# 28_Pins.net
KiCad netlist of a schematic drawn in Altium Designer
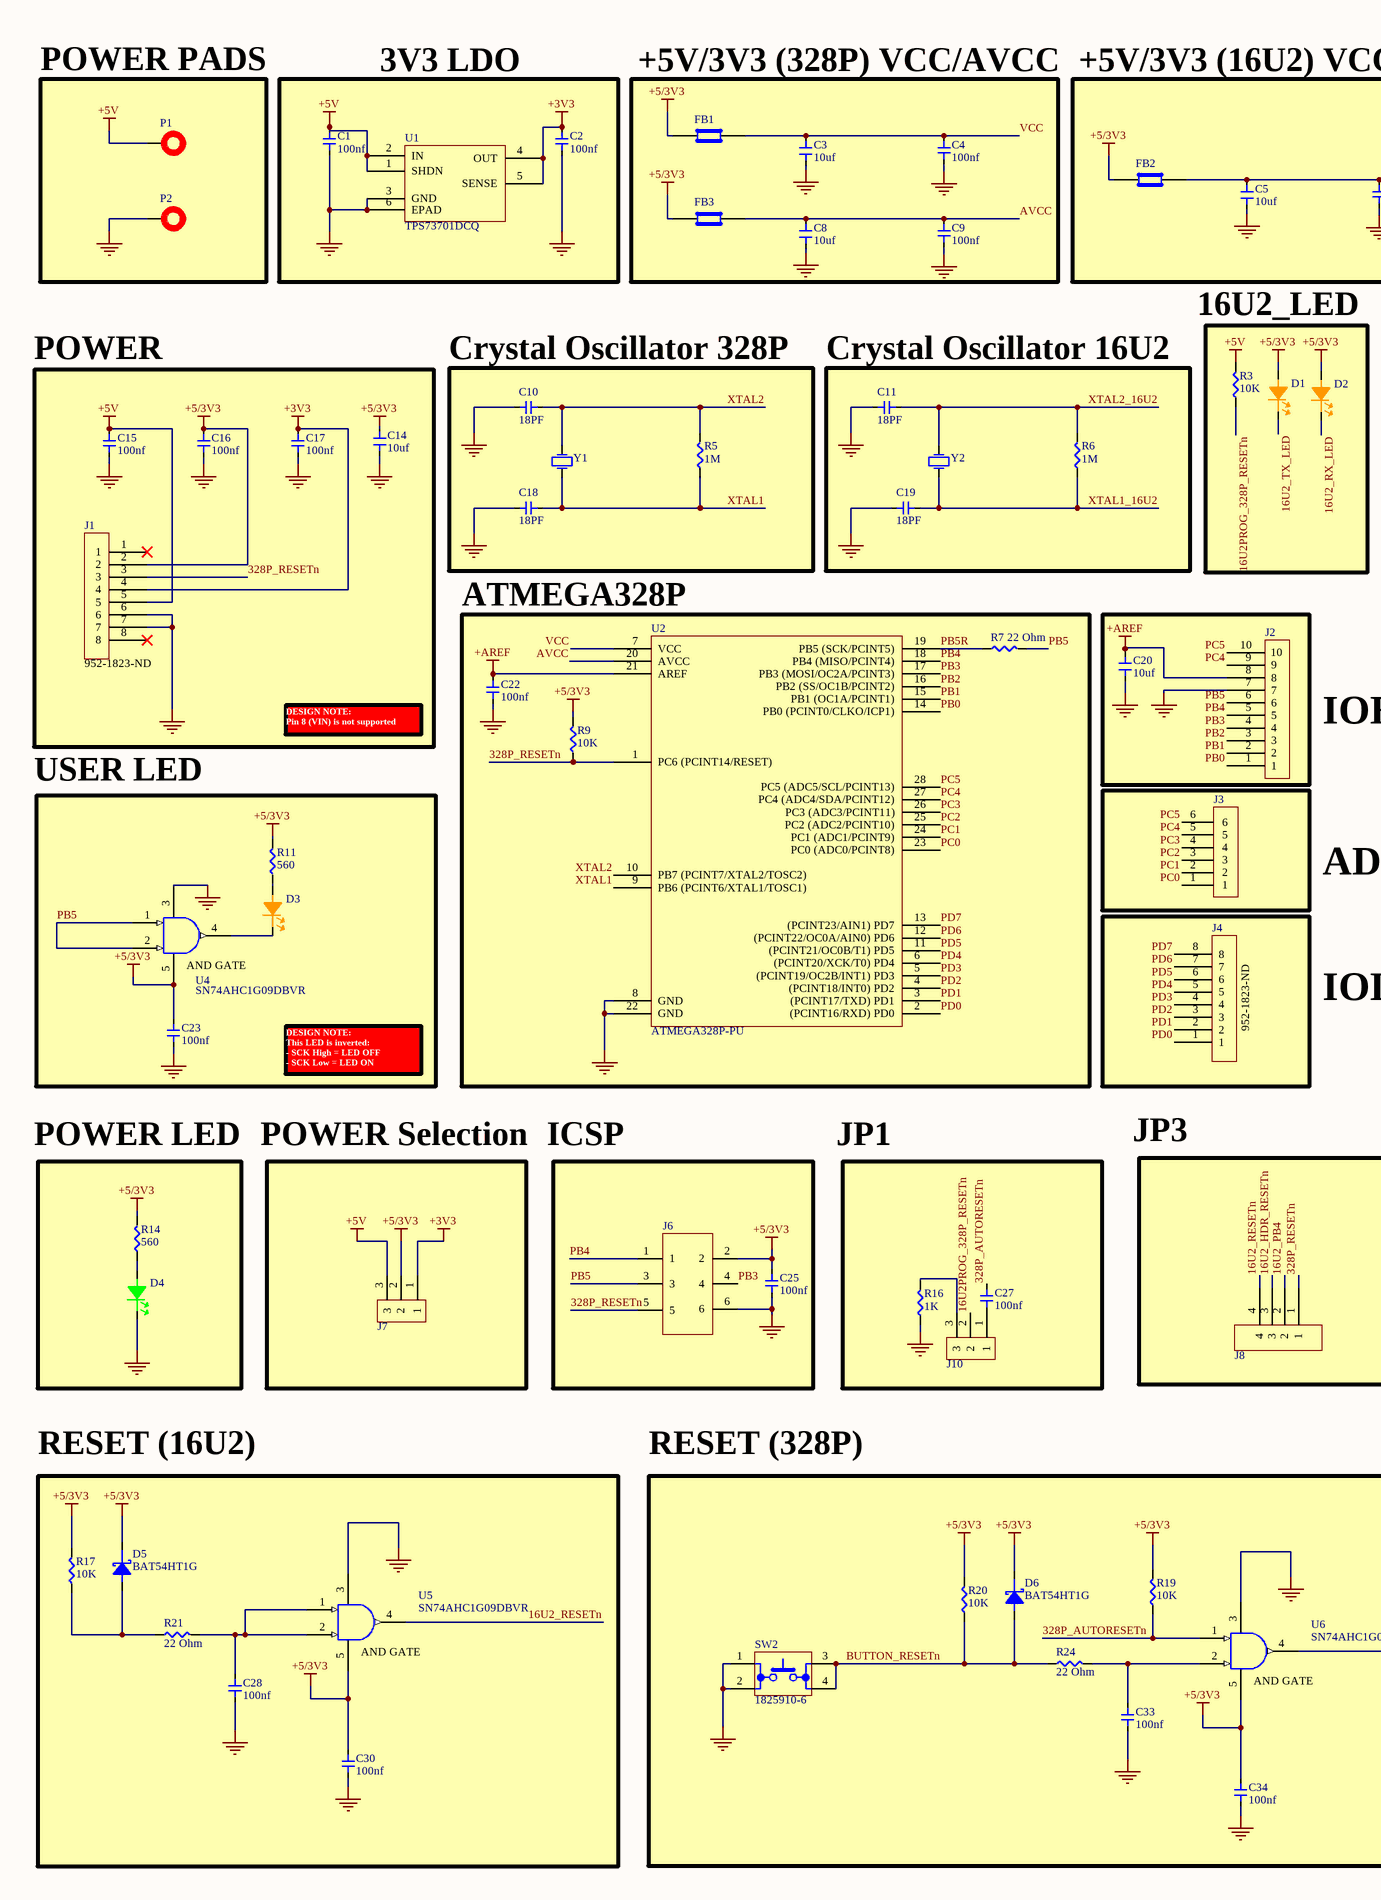
[diagram p0: 28_Pins.SchDoc, left]
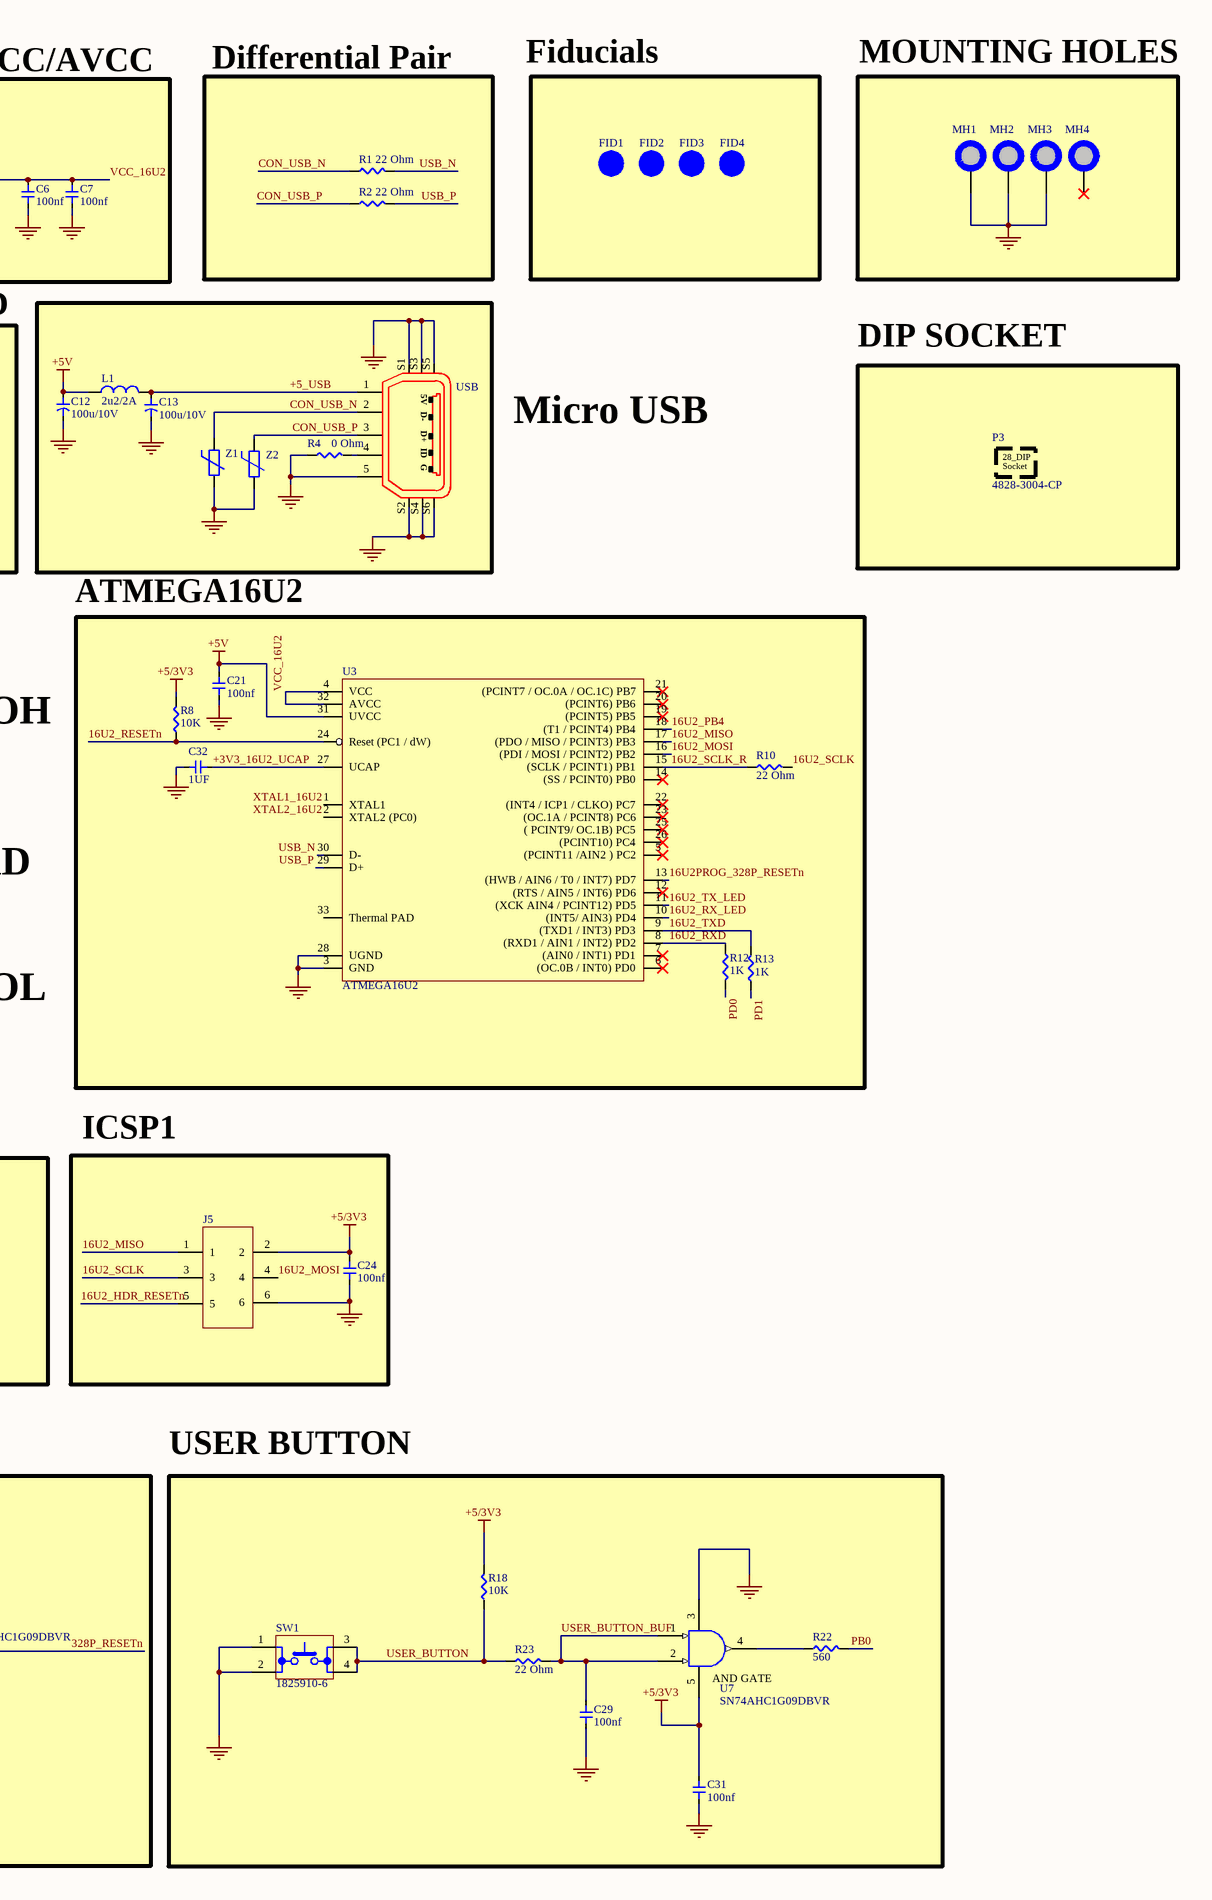
[diagram p1: 28_Pins.SchDoc, right]

(export (version "E")
  (design (tool "Eeschema 10.0.6"))
  (components
    (comp (ref "C1")
      (value "100nf")
      (footprint "Cap_100nf")
      (description "C Series 0805 0.1 uF 50 V ±10 % Tolerance X7R SMT Multilayer Ceramic Capacitor")
      (fields
        (field (name "MANUFACTURER") "TDK")
        (field (name "MANUFACTURER PART NUMBER") "C2012X7R1H104K085AA")
      )
      (libsource (lib "Schlib") (part "C2012X7R1H104K085AA"))
    )
    (comp (ref "C2")
      (value "100nf")
      (footprint "Cap_100nf")
      (description "C Series 0805 0.1 uF 50 V ±10 % Tolerance X7R SMT Multilayer Ceramic Capacitor")
      (fields
        (field (name "MANUFACTURER") "TDK")
        (field (name "MANUFACTURER PART NUMBER") "C2012X7R1H104K085AA")
      )
      (libsource (lib "Schlib") (part "C2012X7R1H104K085AA"))
    )
    (comp (ref "C3")
      (value "10uf")
      (footprint "Cap_10uf")
      (fields
        (field (name "MANUFACTURER") "TDK")
        (field (name "MANUFACTURER PART NUMBER") "C2012X5R1C106M125AC")
        (field (name "TOLERANCE") "20%")
      )
      (libsource (lib "Schlib") (part "C2012X5R1C106M125AC"))
    )
    (comp (ref "C4")
      (value "100nf")
      (footprint "Cap_100nf")
      (description "C Series 0805 0.1 uF 50 V ±10 % Tolerance X7R SMT Multilayer Ceramic Capacitor")
      (fields
        (field (name "MANUFACTURER") "TDK")
        (field (name "MANUFACTURER PART NUMBER") "C2012X7R1H104K085AA")
      )
      (libsource (lib "Schlib") (part "C2012X7R1H104K085AA"))
    )
    (comp (ref "C5")
      (value "10uf")
      (footprint "Cap_10uf")
      (fields
        (field (name "MANUFACTURER") "TDK")
        (field (name "MANUFACTURER PART NUMBER") "C2012X5R1C106M125AC")
        (field (name "TOLERANCE") "20%")
      )
      (libsource (lib "Schlib") (part "C2012X5R1C106M125AC"))
    )
    (comp (ref "C6")
      (value "100nf")
      (footprint "Cap_100nf")
      (description "C Series 0805 0.1 uF 50 V ±10 % Tolerance X7R SMT Multilayer Ceramic Capacitor")
      (fields
        (field (name "MANUFACTURER") "TDK")
        (field (name "MANUFACTURER PART NUMBER") "C2012X7R1H104K085AA")
      )
      (libsource (lib "Schlib") (part "C2012X7R1H104K085AA"))
    )
    (comp (ref "C7")
      (value "100nf")
      (footprint "Cap_100nf")
      (description "C Series 0805 0.1 uF 50 V ±10 % Tolerance X7R SMT Multilayer Ceramic Capacitor")
      (fields
        (field (name "MANUFACTURER") "TDK")
        (field (name "MANUFACTURER PART NUMBER") "C2012X7R1H104K085AA")
      )
      (libsource (lib "Schlib") (part "C2012X7R1H104K085AA"))
    )
    (comp (ref "C8")
      (value "10uf")
      (footprint "Cap_10uf")
      (fields
        (field (name "MANUFACTURER") "TDK")
        (field (name "MANUFACTURER PART NUMBER") "C2012X5R1C106M125AC")
        (field (name "TOLERANCE") "20%")
      )
      (libsource (lib "Schlib") (part "C2012X5R1C106M125AC"))
    )
    (comp (ref "C9")
      (value "100nf")
      (footprint "Cap_100nf")
      (description "C Series 0805 0.1 uF 50 V ±10 % Tolerance X7R SMT Multilayer Ceramic Capacitor")
      (fields
        (field (name "MANUFACTURER") "TDK")
        (field (name "MANUFACTURER PART NUMBER") "C2012X7R1H104K085AA")
      )
      (libsource (lib "Schlib") (part "C2012X7R1H104K085AA"))
    )
    (comp (ref "C10")
      (value "18PF")
      (footprint "Cap_100nf")
      (description "Ceramic Capacitor 0.079Lx0.049W 2.00mmx1.25mm C0G NP0 ±5% 18pF")
      (fields
        (field (name "MANUFACTURER") "KEMET")
        (field (name "MANUFACTURER PART NUMBER") "C0805C180J5GACTU")
      )
      (libsource (lib "Schlib") (part "C0805C180J5GACTU"))
    )
    (comp (ref "C11")
      (value "18PF")
      (footprint "Cap_100nf")
      (description "Ceramic Capacitor 0.079Lx0.049W 2.00mmx1.25mm C0G NP0 ±5% 18pF")
      (fields
        (field (name "MANUFACTURER") "KEMET")
        (field (name "MANUFACTURER PART NUMBER") "C0805C180J5GACTU")
      )
      (libsource (lib "Schlib") (part "C0805C180J5GACTU"))
    )
    (comp (ref "C12")
      (value "100u/10V")
      (footprint "Capacitor100uf")
      (description "Radial Can - SMD ALUMINUM ELECTROLYTIC CAPACITOR S 10V 100muF ±20% 0.197Dia 5.00mm")
      (fields
        (field (name "MANUFACTURER") "Panasonic")
        (field (name "MANUFACTURER PART NUMBER") "EEE-1AA101WR")
      )
      (libsource (lib "Schlib") (part "EEE-1AA101WR"))
    )
    (comp (ref "C13")
      (value "100u/10V")
      (footprint "Capacitor100uf")
      (description "Radial Can - SMD ALUMINUM ELECTROLYTIC CAPACITOR S 10V 100muF ±20% 0.197Dia 5.00mm")
      (fields
        (field (name "MANUFACTURER") "Panasonic")
        (field (name "MANUFACTURER PART NUMBER") "EEE-1AA101WR")
      )
      (libsource (lib "Schlib") (part "EEE-1AA101WR"))
    )
    (comp (ref "C14")
      (value "10uf")
      (footprint "Cap_10uf")
      (fields
        (field (name "MANUFACTURER") "TDK")
        (field (name "MANUFACTURER PART NUMBER") "C2012X5R1C106M125AC")
        (field (name "TOLERANCE") "20%")
      )
      (libsource (lib "Schlib") (part "C2012X5R1C106M125AC"))
    )
    (comp (ref "C15")
      (value "100nf")
      (footprint "Cap_100nf")
      (description "C Series 0805 0.1 uF 50 V ±10 % Tolerance X7R SMT Multilayer Ceramic Capacitor")
      (fields
        (field (name "MANUFACTURER") "TDK")
        (field (name "MANUFACTURER PART NUMBER") "C2012X7R1H104K085AA")
      )
      (libsource (lib "Schlib") (part "C2012X7R1H104K085AA"))
    )
    (comp (ref "C16")
      (value "100nf")
      (footprint "Cap_100nf")
      (description "C Series 0805 0.1 uF 50 V ±10 % Tolerance X7R SMT Multilayer Ceramic Capacitor")
      (fields
        (field (name "MANUFACTURER") "TDK")
        (field (name "MANUFACTURER PART NUMBER") "C2012X7R1H104K085AA")
      )
      (libsource (lib "Schlib") (part "C2012X7R1H104K085AA"))
    )
    (comp (ref "C17")
      (value "100nf")
      (footprint "Cap_100nf")
      (description "C Series 0805 0.1 uF 50 V ±10 % Tolerance X7R SMT Multilayer Ceramic Capacitor")
      (fields
        (field (name "MANUFACTURER") "TDK")
        (field (name "MANUFACTURER PART NUMBER") "C2012X7R1H104K085AA")
      )
      (libsource (lib "Schlib") (part "C2012X7R1H104K085AA"))
    )
    (comp (ref "C18")
      (value "18PF")
      (footprint "Cap_100nf")
      (description "Ceramic Capacitor 0.079Lx0.049W 2.00mmx1.25mm C0G NP0 ±5% 18pF")
      (fields
        (field (name "MANUFACTURER") "KEMET")
        (field (name "MANUFACTURER PART NUMBER") "C0805C180J5GACTU")
      )
      (libsource (lib "Schlib") (part "C0805C180J5GACTU"))
    )
    (comp (ref "C19")
      (value "18PF")
      (footprint "Cap_100nf")
      (description "Ceramic Capacitor 0.079Lx0.049W 2.00mmx1.25mm C0G NP0 ±5% 18pF")
      (fields
        (field (name "MANUFACTURER") "KEMET")
        (field (name "MANUFACTURER PART NUMBER") "C0805C180J5GACTU")
      )
      (libsource (lib "Schlib") (part "C0805C180J5GACTU"))
    )
    (comp (ref "C20")
      (value "10uf")
      (footprint "Cap_10uf")
      (fields
        (field (name "MANUFACTURER") "TDK")
        (field (name "MANUFACTURER PART NUMBER") "C2012X5R1C106M125AC")
        (field (name "TOLERANCE") "20%")
      )
      (libsource (lib "Schlib") (part "C2012X5R1C106M125AC"))
    )
    (comp (ref "C21")
      (value "100nf")
      (footprint "Cap_100nf")
      (description "C Series 0805 0.1 uF 50 V ±10 % Tolerance X7R SMT Multilayer Ceramic Capacitor")
      (fields
        (field (name "MANUFACTURER") "TDK")
        (field (name "MANUFACTURER PART NUMBER") "C2012X7R1H104K085AA")
      )
      (libsource (lib "Schlib") (part "C2012X7R1H104K085AA"))
    )
    (comp (ref "C22")
      (value "100nf")
      (footprint "Cap_100nf")
      (description "C Series 0805 0.1 uF 50 V ±10 % Tolerance X7R SMT Multilayer Ceramic Capacitor")
      (fields
        (field (name "MANUFACTURER") "TDK")
        (field (name "MANUFACTURER PART NUMBER") "C2012X7R1H104K085AA")
      )
      (libsource (lib "Schlib") (part "C2012X7R1H104K085AA"))
    )
    (comp (ref "C23")
      (value "100nf")
      (footprint "Cap_100nf")
      (description "C Series 0805 0.1 uF 50 V ±10 % Tolerance X7R SMT Multilayer Ceramic Capacitor")
      (fields
        (field (name "MANUFACTURER") "TDK")
        (field (name "MANUFACTURER PART NUMBER") "C2012X7R1H104K085AA")
      )
      (libsource (lib "Schlib") (part "C2012X7R1H104K085AA"))
    )
    (comp (ref "C24")
      (value "100nf")
      (footprint "Cap_100nf")
      (description "C Series 0805 0.1 uF 50 V ±10 % Tolerance X7R SMT Multilayer Ceramic Capacitor")
      (fields
        (field (name "MANUFACTURER") "TDK")
        (field (name "MANUFACTURER PART NUMBER") "C2012X7R1H104K085AA")
      )
      (libsource (lib "Schlib") (part "C2012X7R1H104K085AA"))
    )
    (comp (ref "C25")
      (value "100nf")
      (footprint "Cap_100nf")
      (description "C Series 0805 0.1 uF 50 V ±10 % Tolerance X7R SMT Multilayer Ceramic Capacitor")
      (fields
        (field (name "MANUFACTURER") "TDK")
        (field (name "MANUFACTURER PART NUMBER") "C2012X7R1H104K085AA")
      )
      (libsource (lib "Schlib") (part "C2012X7R1H104K085AA"))
    )
    (comp (ref "C27")
      (value "100nf")
      (footprint "Cap_100nf")
      (description "C Series 0805 0.1 uF 50 V ±10 % Tolerance X7R SMT Multilayer Ceramic Capacitor")
      (fields
        (field (name "MANUFACTURER") "TDK")
        (field (name "MANUFACTURER PART NUMBER") "C2012X7R1H104K085AA")
      )
      (libsource (lib "Schlib") (part "C2012X7R1H104K085AA"))
    )
    (comp (ref "C28")
      (value "100nf")
      (footprint "Cap_100nf")
      (description "C Series 0805 0.1 uF 50 V ±10 % Tolerance X7R SMT Multilayer Ceramic Capacitor")
      (fields
        (field (name "MANUFACTURER") "TDK")
        (field (name "MANUFACTURER PART NUMBER") "C2012X7R1H104K085AA")
      )
      (libsource (lib "Schlib") (part "C2012X7R1H104K085AA"))
    )
    (comp (ref "C29")
      (value "100nf")
      (footprint "Cap_100nf")
      (description "C Series 0805 0.1 uF 50 V ±10 % Tolerance X7R SMT Multilayer Ceramic Capacitor")
      (fields
        (field (name "MANUFACTURER") "TDK")
        (field (name "MANUFACTURER PART NUMBER") "C2012X7R1H104K085AA")
      )
      (libsource (lib "Schlib") (part "C2012X7R1H104K085AA"))
    )
    (comp (ref "C30")
      (value "100nf")
      (footprint "Cap_100nf")
      (description "C Series 0805 0.1 uF 50 V ±10 % Tolerance X7R SMT Multilayer Ceramic Capacitor")
      (fields
        (field (name "MANUFACTURER") "TDK")
        (field (name "MANUFACTURER PART NUMBER") "C2012X7R1H104K085AA")
      )
      (libsource (lib "Schlib") (part "C2012X7R1H104K085AA"))
    )
    (comp (ref "C31")
      (value "100nf")
      (footprint "Cap_100nf")
      (description "C Series 0805 0.1 uF 50 V ±10 % Tolerance X7R SMT Multilayer Ceramic Capacitor")
      (fields
        (field (name "MANUFACTURER") "TDK")
        (field (name "MANUFACTURER PART NUMBER") "C2012X7R1H104K085AA")
      )
      (libsource (lib "Schlib") (part "C2012X7R1H104K085AA"))
    )
    (comp (ref "C32")
      (value "1UF")
      (footprint "Cap_10uf")
      (description "C Series 0805 1 uF 25 V ±10% Tolerance X5R SMT Multilayer Ceramic Capacitor")
      (fields
        (field (name "MANUFACTURER") "TDK")
        (field (name "MANUFACTURER PART NUMBER") "C2012X5R1E105K125AA")
      )
      (libsource (lib "Schlib") (part "C2012X5R1E105K125AA"))
    )
    (comp (ref "C33")
      (value "100nf")
      (footprint "Cap_100nf")
      (description "C Series 0805 0.1 uF 50 V ±10 % Tolerance X7R SMT Multilayer Ceramic Capacitor")
      (fields
        (field (name "MANUFACTURER") "TDK")
        (field (name "MANUFACTURER PART NUMBER") "C2012X7R1H104K085AA")
      )
      (libsource (lib "Schlib") (part "C2012X7R1H104K085AA"))
    )
    (comp (ref "C34")
      (value "100nf")
      (footprint "Cap_100nf")
      (description "C Series 0805 0.1 uF 50 V ±10 % Tolerance X7R SMT Multilayer Ceramic Capacitor")
      (fields
        (field (name "MANUFACTURER") "TDK")
        (field (name "MANUFACTURER PART NUMBER") "C2012X7R1H104K085AA")
      )
      (libsource (lib "Schlib") (part "C2012X7R1H104K085AA"))
    )
    (comp (ref "D1")
      (value "LO L29K-H2K1-24-0-2-R18-Z")
      (footprint "LED Indication")
      (description "LED Uni-Color Orange 610nm Automotive 2-Pin Chip 0603(1608Metric) T/R")
      (fields (field (name "MANUFACTURER") "Osram"))
      (libsource (lib "Schlib") (part "LO L29K-H2K1-24-0-2-R18-Z"))
    )
    (comp (ref "D2")
      (value "LO L29K-H2K1-24-0-2-R18-Z")
      (footprint "LED Indication")
      (description "LED Uni-Color Orange 610nm Automotive 2-Pin Chip 0603(1608Metric) T/R")
      (fields (field (name "MANUFACTURER") "Osram"))
      (libsource (lib "Schlib") (part "LO L29K-H2K1-24-0-2-R18-Z"))
    )
    (comp (ref "D3")
      (value "LO L29K-H2K1-24-0-2-R18-Z")
      (footprint "LED Indication")
      (description "LED Uni-Color Orange 610nm Automotive 2-Pin Chip 0603(1608Metric) T/R")
      (fields (field (name "MANUFACTURER") "Osram"))
      (libsource (lib "Schlib") (part "LO L29K-H2K1-24-0-2-R18-Z"))
    )
    (comp (ref "D4")
      (value "LG L29K-G2J1-24-0-2-R18-Z")
      (footprint "LED Indication")
      (description "LED Uni-Color Green 572nm 2-Pin Chip 0603(1608Metric) T/R")
      (fields (field (name "MANUFACTURER") "Osram"))
      (libsource (lib "Schlib") (part "LG L29K-G2J1-24-0-2-R18-Z"))
    )
    (comp (ref "D5")
      (value "BAT54HT1G")
      (footprint "diode")
      (description "Small Signal Schottky Diode, Single, 30 V, 200 Ma, 800 Mv, 600 Ma, 150 C")
      (fields (field (name "MANUFACTURER") "onsemi"))
      (libsource (lib "Schlib") (part "BAT54HT1G"))
    )
    (comp (ref "D6")
      (value "BAT54HT1G")
      (footprint "diode")
      (description "Small Signal Schottky Diode, Single, 30 V, 200 Ma, 800 Mv, 600 Ma, 150 C")
      (fields (field (name "MANUFACTURER") "onsemi"))
      (libsource (lib "Schlib") (part "BAT54HT1G"))
    )
    (comp (ref "FB1")
      (value "MPZ2012S601AT000")
      (footprint "Cap_10uf")
      (description "Ferrite Beads Multi-Layer Power 600Ohm 25% 100MHz 2A 100mOhm DCR 0805 T/R")
      (fields (field (name "MANUFACTURER") "TDK") (field (name "TOLERANCE") "25%"))
      (libsource (lib "Schlib") (part "MPZ2012S601AT000"))
    )
    (comp (ref "FB2")
      (value "MPZ2012S601AT000")
      (footprint "Cap_10uf")
      (description "Ferrite Beads Multi-Layer Power 600Ohm 25% 100MHz 2A 100mOhm DCR 0805 T/R")
      (fields (field (name "MANUFACTURER") "TDK") (field (name "TOLERANCE") "25%"))
      (libsource (lib "Schlib") (part "MPZ2012S601AT000"))
    )
    (comp (ref "FB3")
      (value "MPZ2012S601AT000")
      (footprint "Cap_10uf")
      (description "Ferrite Beads Multi-Layer Power 600Ohm 25% 100MHz 2A 100mOhm DCR 0805 T/R")
      (fields (field (name "MANUFACTURER") "TDK") (field (name "TOLERANCE") "25%"))
      (libsource (lib "Schlib") (part "MPZ2012S601AT000"))
    )
    (comp (ref "FID1")
      (value "Fid_1MMC")
      (footprint "FID")
      (description "1.2mil")
      (libsource (lib "Schlib") (part "Fid_1MMC"))
    )
    (comp (ref "FID2")
      (value "Fid_1MMC")
      (footprint "FID")
      (description "1.2mil")
      (libsource (lib "Schlib") (part "Fid_1MMC"))
    )
    (comp (ref "FID3")
      (value "Fid_1MMC")
      (footprint "FID")
      (description "1.2mil")
      (libsource (lib "Schlib") (part "Fid_1MMC"))
    )
    (comp (ref "FID4")
      (value "Fid_1MMC")
      (footprint "FID")
      (description "1.2mil")
      (libsource (lib "Schlib") (part "Fid_1MMC"))
    )
    (comp (ref "J1")
      (value "M20-7820842")
      (footprint "header_8pins")
      (description "8 contacts,2.54mm (0.1) Pitch SIL Vertical PC Tail Socket Assembly, selective gold + tin,")
      (fields (field (name "MANUFACTURER") "Harwin") (field (name "SUPPLIER PART NUMBER 1") "952-1823-ND"))
      (libsource (lib "Schlib") (part "M20-7820842"))
    )
    (comp (ref "J2")
      (value "M20-7821046")
      (footprint "female header")
      (description "Conn Socket Strip Receptacle 10 Position 2.54mm Solder Straight Through Hole Tube")
      (fields (field (name "MANUFACTURER") "Harwin"))
      (libsource (lib "Schlib") (part "M20-7821046"))
    )
    (comp (ref "J3")
      (value "M20-7820646")
      (footprint "header_6pins")
      (description "Conn Socket Strip Receptacle 6 Position 2.54mm Solder Straight Through Hole Tube")
      (fields (field (name "MANUFACTURER") "Harwin"))
      (libsource (lib "Schlib") (part "M20-7820646"))
    )
    (comp (ref "J4")
      (value "M20-7820842")
      (footprint "header_8pins")
      (description "8 contacts,2.54mm (0.1) Pitch SIL Vertical PC Tail Socket Assembly, selective gold + tin,")
      (fields (field (name "MANUFACTURER") "Harwin") (field (name "SUPPLIER PART NUMBER 1") "952-1823-ND"))
      (libsource (lib "") (part "M20-7820842_1"))
    )
    (comp (ref "J5")
      (value "67997-106HLF")
      (footprint "header_6pins")
      (description "Conn; Rect; Header; Unshrouded; 6 Pos; 2.54mm Pitch; 2-Row; Thru-Hole; BergStik")
      (fields (field (name "MANUFACTURER") "Amphenol Communications Solutions"))
      (libsource (lib "Schlib") (part "67997-106HLF"))
    )
    (comp (ref "J6")
      (value "67997-106HLF")
      (footprint "header_6pins")
      (description "Conn; Rect; Header; Unshrouded; 6 Pos; 2.54mm Pitch; 2-Row; Thru-Hole; BergStik")
      (fields (field (name "MANUFACTURER") "Amphenol Communications Solutions"))
      (libsource (lib "Schlib") (part "67997-106HLF"))
    )
    (comp (ref "J7")
      (value "68000-103HLF")
      (footprint "header_3pins")
      (description "Pin Header, Board-to-Board, 2.54 mm, 1 Rows, 3 Contacts, Through Hole, FCI BergStik II 68000")
      (fields (field (name "MANUFACTURER") "Amphenol Communications Solutions"))
      (libsource (lib "Schlib") (part "68000-103HLF"))
    )
    (comp (ref "J8")
      (value "68001-204HLF")
      (footprint "header_4pins")
      (description "Conn Unshrouded Header HDR 4 POS 2.54mm Solder ST Top Entry Thru-Hole BergStik® Bulk")
      (fields (field (name "MANUFACTURER") "Amphenol Communications Solutions"))
      (libsource (lib "Schlib") (part "68001-204HLF"))
    )
    (comp (ref "J10")
      (value "68000-103HLF")
      (footprint "header_3pins")
      (description "Pin Header, Board-to-Board, 2.54 mm, 1 Rows, 3 Contacts, Through Hole, FCI BergStik II 68000")
      (fields (field (name "MANUFACTURER") "Amphenol Communications Solutions"))
      (libsource (lib "Schlib") (part "68000-103HLF"))
    )
    (comp (ref "L1")
      (value "2u2/2A")
      (footprint "inductor")
      (description "General Purpose Inductor, 2.2uH, 20%, 1 Element, Ferrite-Core, SMD, 1210")
      (fields
        (field (name "MANUFACTURER") "KEMET")
        (field (name "MANUFACTURER PART NUMBER") "L1210R2R2MDWIT")
      )
      (libsource (lib "Schlib") (part "L1210R2R2MDWIT"))
    )
    (comp (ref "MH1")
      (value "Mounting Holes")
      (footprint "MH")
      (libsource (lib "Schlib") (part "Mounting Holes"))
    )
    (comp (ref "MH2")
      (value "Mounting Holes")
      (footprint "MH")
      (libsource (lib "Schlib") (part "Mounting Holes"))
    )
    (comp (ref "MH3")
      (value "Mounting Holes")
      (footprint "MH")
      (libsource (lib "Schlib") (part "Mounting Holes"))
    )
    (comp (ref "MH4")
      (value "Mounting Holes")
      (footprint "MH")
      (libsource (lib "Schlib") (part "Mounting Holes"))
    )
    (comp (ref "P1") (value "pad") (footprint "MH") (libsource (lib "Schlib") (part "pad")))
    (comp (ref "P2") (value "pad") (footprint "MH") (libsource (lib "Schlib") (part "pad")))
    (comp (ref "P3")
      (value "4828-3004-CP")
      (footprint "dip_socket")
      (description "IC Socket, DIP28, 28 Contact(s), 2.54mm Term Pitch, 7.62mm Row Spacing, Solder")
      (fields (field (name "MANUFACTURER") "3M"))
      (libsource (lib "Schlib") (part "4828-3004-CP"))
    )
    (comp (ref "R1")
      (value "22 Ohm")
      (footprint "Resistor_1M")
      (description "Res Thick Film 0805 22 Ohm 1% 0.125W(1/8W) ±100ppm/C Pad SMD T/R")
      (fields
        (field (name "MANUFACTURER") "Yageo Group")
        (field (name "MANUFACTURER PART NUMBER") "RC0805FR-0722RL")
      )
      (libsource (lib "Schlib") (part "RC0805FR-0722RL"))
    )
    (comp (ref "R2")
      (value "22 Ohm")
      (footprint "Resistor_1M")
      (description "Res Thick Film 0805 22 Ohm 1% 0.125W(1/8W) ±100ppm/C Pad SMD T/R")
      (fields
        (field (name "MANUFACTURER") "Yageo Group")
        (field (name "MANUFACTURER PART NUMBER") "RC0805FR-0722RL")
      )
      (libsource (lib "Schlib") (part "RC0805FR-0722RL"))
    )
    (comp (ref "R3")
      (value "10K")
      (footprint "Resistor_1M")
      (description "Res Thick Film 0805 10K Ohm 1% 0.125W(1/8W) +/-100ppm/C Epoxy Pad SMD T/R")
      (fields
        (field (name "MANUFACTURER") "Yageo Group")
        (field (name "MANUFACTURER PART NUMBER") "RC0805FR-0710KL")
      )
      (libsource (lib "Schlib") (part "RC0805FR-0710KL"))
    )
    (comp (ref "R4")
      (value "0 Ohm")
      (footprint "Resistor_1M")
      (description "GENERAL PURPOSE CHIP RESISTOR Metal Glaze/thick Film, 0.125W, 0ohm, Surface Mount, 0805")
      (fields
        (field (name "MANUFACTURER") "Yageo Group")
        (field (name "MANUFACTURER PART NUMBER") "RC0805JR-070RL")
      )
      (libsource (lib "Schlib") (part "RC0805JR-070RL"))
    )
    (comp (ref "R5")
      (value "1M")
      (footprint "Resistor_1M")
      (description "125Mw Thick Film Resistors 100Ppm/ 1% 1M 0805 Chip Resistor Surface Mount Rohs")
      (fields
        (field (name "MANUFACTURER") "Yageo Group")
        (field (name "MANUFACTURER PART NUMBER") "RC0805FR-071ML")
      )
      (libsource (lib "Schlib") (part "RC0805FR-071ML"))
    )
    (comp (ref "R6")
      (value "1M")
      (footprint "Resistor_1M")
      (description "125Mw Thick Film Resistors 100Ppm/ 1% 1M 0805 Chip Resistor Surface Mount Rohs")
      (fields
        (field (name "MANUFACTURER") "Yageo Group")
        (field (name "MANUFACTURER PART NUMBER") "RC0805FR-071ML")
      )
      (libsource (lib "Schlib") (part "RC0805FR-071ML"))
    )
    (comp (ref "R7")
      (value "22 Ohm")
      (footprint "Resistor_1M")
      (description "Res Thick Film 0805 22 Ohm 1% 0.125W(1/8W) ±100ppm/C Pad SMD T/R")
      (fields
        (field (name "MANUFACTURER") "Yageo Group")
        (field (name "MANUFACTURER PART NUMBER") "RC0805FR-0722RL")
      )
      (libsource (lib "Schlib") (part "RC0805FR-0722RL"))
    )
    (comp (ref "R8")
      (value "10K")
      (footprint "Resistor_1M")
      (description "Res Thick Film 0805 10K Ohm 1% 0.125W(1/8W) +/-100ppm/C Epoxy Pad SMD T/R")
      (fields
        (field (name "MANUFACTURER") "Yageo Group")
        (field (name "MANUFACTURER PART NUMBER") "RC0805FR-0710KL")
      )
      (libsource (lib "Schlib") (part "RC0805FR-0710KL"))
    )
    (comp (ref "R9")
      (value "10K")
      (footprint "Resistor_1M")
      (description "Res Thick Film 0805 10K Ohm 1% 0.125W(1/8W) +/-100ppm/C Epoxy Pad SMD T/R")
      (fields
        (field (name "MANUFACTURER") "Yageo Group")
        (field (name "MANUFACTURER PART NUMBER") "RC0805FR-0710KL")
      )
      (libsource (lib "Schlib") (part "RC0805FR-0710KL"))
    )
    (comp (ref "R10")
      (value "22 Ohm")
      (footprint "Resistor_1M")
      (description "Res Thick Film 0805 22 Ohm 1% 0.125W(1/8W) ±100ppm/C Pad SMD T/R")
      (fields
        (field (name "MANUFACTURER") "Yageo Group")
        (field (name "MANUFACTURER PART NUMBER") "RC0805FR-0722RL")
      )
      (libsource (lib "Schlib") (part "RC0805FR-0722RL"))
    )
    (comp (ref "R11")
      (value "560")
      (footprint "Resistor_1M")
      (description "Res Thick Film 0805 560 Ohm 1% 0.125W(1/8W) ±100ppm/C Pad SMD T/R")
      (fields
        (field (name "MANUFACTURER") "Yageo Group")
        (field (name "MANUFACTURER PART NUMBER") "RC0805FR-07560RL")
      )
      (libsource (lib "Schlib") (part "RC0805FR-07560RL"))
    )
    (comp (ref "R12")
      (value "1K")
      (footprint "Resistor_1M")
      (description "125Mw Thick Film Resistors 100Ppm/ 1% 1K 0805 Chip Resistor Surface Mount Rohs")
      (fields
        (field (name "MANUFACTURER") "Yageo Group")
        (field (name "MANUFACTURER PART NUMBER") "RC0805FR-071KL")
      )
      (libsource (lib "Schlib") (part "RC0805FR-071KL"))
    )
    (comp (ref "R13")
      (value "1K")
      (footprint "Resistor_1M")
      (description "125Mw Thick Film Resistors 100Ppm/ 1% 1K 0805 Chip Resistor Surface Mount Rohs")
      (fields
        (field (name "MANUFACTURER") "Yageo Group")
        (field (name "MANUFACTURER PART NUMBER") "RC0805FR-071KL")
      )
      (libsource (lib "Schlib") (part "RC0805FR-071KL"))
    )
    (comp (ref "R14")
      (value "560")
      (footprint "Resistor_1M")
      (description "Res Thick Film 0805 560 Ohm 1% 0.125W(1/8W) ±100ppm/C Pad SMD T/R")
      (fields
        (field (name "MANUFACTURER") "Yageo Group")
        (field (name "MANUFACTURER PART NUMBER") "RC0805FR-07560RL")
      )
      (libsource (lib "Schlib") (part "RC0805FR-07560RL"))
    )
    (comp (ref "R16")
      (value "1K")
      (footprint "Resistor_1M")
      (description "125Mw Thick Film Resistors 100Ppm/ 1% 1K 0805 Chip Resistor Surface Mount Rohs")
      (fields
        (field (name "MANUFACTURER") "Yageo Group")
        (field (name "MANUFACTURER PART NUMBER") "RC0805FR-071KL")
      )
      (libsource (lib "Schlib") (part "RC0805FR-071KL"))
    )
    (comp (ref "R17")
      (value "10K")
      (footprint "Resistor_1M")
      (description "Res Thick Film 0805 10K Ohm 1% 0.125W(1/8W) +/-100ppm/C Epoxy Pad SMD T/R")
      (fields
        (field (name "MANUFACTURER") "Yageo Group")
        (field (name "MANUFACTURER PART NUMBER") "RC0805FR-0710KL")
      )
      (libsource (lib "Schlib") (part "RC0805FR-0710KL"))
    )
    (comp (ref "R18")
      (value "10K")
      (footprint "Resistor_1M")
      (description "Res Thick Film 0805 10K Ohm 1% 0.125W(1/8W) +/-100ppm/C Epoxy Pad SMD T/R")
      (fields
        (field (name "MANUFACTURER") "Yageo Group")
        (field (name "MANUFACTURER PART NUMBER") "RC0805FR-0710KL")
      )
      (libsource (lib "Schlib") (part "RC0805FR-0710KL"))
    )
    (comp (ref "R19")
      (value "10K")
      (footprint "Resistor_1M")
      (description "Res Thick Film 0805 10K Ohm 1% 0.125W(1/8W) +/-100ppm/C Epoxy Pad SMD T/R")
      (fields
        (field (name "MANUFACTURER") "Yageo Group")
        (field (name "MANUFACTURER PART NUMBER") "RC0805FR-0710KL")
      )
      (libsource (lib "Schlib") (part "RC0805FR-0710KL"))
    )
    (comp (ref "R20")
      (value "10K")
      (footprint "Resistor_1M")
      (description "Res Thick Film 0805 10K Ohm 1% 0.125W(1/8W) +/-100ppm/C Epoxy Pad SMD T/R")
      (fields
        (field (name "MANUFACTURER") "Yageo Group")
        (field (name "MANUFACTURER PART NUMBER") "RC0805FR-0710KL")
      )
      (libsource (lib "Schlib") (part "RC0805FR-0710KL"))
    )
    (comp (ref "R21")
      (value "22 Ohm")
      (footprint "Resistor_1M")
      (description "Res Thick Film 0805 22 Ohm 1% 0.125W(1/8W) ±100ppm/C Pad SMD T/R")
      (fields
        (field (name "MANUFACTURER") "Yageo Group")
        (field (name "MANUFACTURER PART NUMBER") "RC0805FR-0722RL")
      )
      (libsource (lib "Schlib") (part "RC0805FR-0722RL"))
    )
    (comp (ref "R22")
      (value "560")
      (footprint "Resistor_1M")
      (description "Res Thick Film 0805 560 Ohm 1% 0.125W(1/8W) ±100ppm/C Pad SMD T/R")
      (fields
        (field (name "MANUFACTURER") "Yageo Group")
        (field (name "MANUFACTURER PART NUMBER") "RC0805FR-07560RL")
      )
      (libsource (lib "Schlib") (part "RC0805FR-07560RL"))
    )
    (comp (ref "R23")
      (value "22 Ohm")
      (footprint "Resistor_1M")
      (description "Res Thick Film 0805 22 Ohm 1% 0.125W(1/8W) ±100ppm/C Pad SMD T/R")
      (fields
        (field (name "MANUFACTURER") "Yageo Group")
        (field (name "MANUFACTURER PART NUMBER") "RC0805FR-0722RL")
      )
      (libsource (lib "Schlib") (part "RC0805FR-0722RL"))
    )
    (comp (ref "R24")
      (value "22 Ohm")
      (footprint "Resistor_1M")
      (description "Res Thick Film 0805 22 Ohm 1% 0.125W(1/8W) ±100ppm/C Pad SMD T/R")
      (fields
        (field (name "MANUFACTURER") "Yageo Group")
        (field (name "MANUFACTURER PART NUMBER") "RC0805FR-0722RL")
      )
      (libsource (lib "Schlib") (part "RC0805FR-0722RL"))
    )
    (comp (ref "SW1")
      (value "1825910-6")
      (footprint "Switch")
      (description "Switch Tactile OFF (ON) SPST Round Button PC Pins 0.05A 24VDC 1.57N Thru-Hole Loose")
      (fields (field (name "MANUFACTURER") "TE Connectivity"))
      (libsource (lib "Schlib") (part "1825910-6"))
    )
    (comp (ref "SW2")
      (value "1825910-6")
      (footprint "Switch")
      (description "Switch Tactile OFF (ON) SPST Round Button PC Pins 0.05A 24VDC 1.57N Thru-Hole Loose")
      (fields (field (name "MANUFACTURER") "TE Connectivity"))
      (libsource (lib "Schlib") (part "1825910-6"))
    )
    (comp (ref "U1")
      (value "TPS73701DCQ")
      (footprint "LDO")
      (description "Low Drop Out (LDO) Regulator Position 1.2 Volt to 5.5 Volt 1A 6-Pin(5+Tab) SOT-223")
      (fields (field (name "MANUFACTURER") "Texas Instruments"))
      (libsource (lib "Schlib") (part "TPS73701DCQ"))
    )
    (comp (ref "U2")
      (value "ATMEGA328P-PU")
      (footprint "DIP28")
      (description "Microchip - ATMEGA328P-PU - Microcontroller Mcu, 8 Bit, Atmega, 20MHZ, DIP-28")
      (fields (field (name "MANUFACTURER") "Microchip"))
      (libsource (lib "Schlib") (part "ATMEGA328P-PU"))
    )
    (comp (ref "U3")
      (value "ATMEGA16U2")
      (footprint "ATMEGA16U2")
      (description "8-bit AVR MCU, 16 KB, 512 Bytes, 16 MHz, 2.7 to 5.5V, VQFN-32, RoHS")
      (fields
        (field (name "MANUFACTURER") "Microchip")
        (field (name "MANUFACTURER PART NUMBER") "ATMEGA16U2-MU")
      )
      (libsource (lib "Schlib") (part "ATMEGA16U2"))
    )
    (comp (ref "U4")
      (value "SN74AHC1G09DBVR")
      (footprint "AND")
      (description "1-ch, 2-input 2-V to 5.5-V high-speed (9 ns) AND gate with open-drain outputs 5-SOT-23 -55 to 125")
      (fields (field (name "MANUFACTURER") "Texas Instruments"))
      (libsource (lib "Schlib") (part "SN74AHC1G09DBVR"))
    )
    (comp (ref "U5")
      (value "SN74AHC1G09DBVR")
      (footprint "AND")
      (description "1-ch, 2-input 2-V to 5.5-V high-speed (9 ns) AND gate with open-drain outputs 5-SOT-23 -55 to 125")
      (fields (field (name "MANUFACTURER") "Texas Instruments"))
      (libsource (lib "Schlib") (part "SN74AHC1G09DBVR"))
    )
    (comp (ref "U6")
      (value "SN74AHC1G09DBVR")
      (footprint "AND")
      (description "1-ch, 2-input 2-V to 5.5-V high-speed (9 ns) AND gate with open-drain outputs 5-SOT-23 -55 to 125")
      (fields (field (name "MANUFACTURER") "Texas Instruments"))
      (libsource (lib "Schlib") (part "SN74AHC1G09DBVR"))
    )
    (comp (ref "U7")
      (value "SN74AHC1G09DBVR")
      (footprint "AND")
      (description "1-ch, 2-input 2-V to 5.5-V high-speed (9 ns) AND gate with open-drain outputs 5-SOT-23 -55 to 125")
      (fields (field (name "MANUFACTURER") "Texas Instruments"))
      (libsource (lib "Schlib") (part "SN74AHC1G09DBVR"))
    )
    (comp (ref "USB")
      (value "10118193-0001LF")
      (footprint "AMPHENOL_10118193-0001LF")
      (description "USB - micro B USB 2.0 Receptacle Connector 5 Position Surface Mount, Right Angle, Horizontal")
      (fields (field (name "MANUFACTURER") "Amphenol Communications Solutions"))
      (libsource (lib "Schlib") (part "10118193-0001LF"))
    )
    (comp (ref "Y1")
      (value "ABM7-16.000MHZ-D2Y-T")
      (footprint "crystal")
      (description "Crystal 16MHz ±20ppm (Tol) ±30ppm (Stability) 18pF FUND 50Ohm 2-Pin Mini-CSMD T/R")
      (fields (field (name "MANUFACTURER") "Abracon") (field (name "TOLERANCE") "0.002%"))
      (libsource (lib "Schlib") (part "ABM7-16.000MHZ-D2Y-T"))
    )
    (comp (ref "Y2")
      (value "ABM7-16.000MHZ-D2Y-T")
      (footprint "crystal")
      (description "Crystal 16MHz ±20ppm (Tol) ±30ppm (Stability) 18pF FUND 50Ohm 2-Pin Mini-CSMD T/R")
      (fields (field (name "MANUFACTURER") "Abracon") (field (name "TOLERANCE") "0.002%"))
      (libsource (lib "Schlib") (part "ABM7-16.000MHZ-D2Y-T"))
    )
    (comp (ref "Z1")
      (value "CG0603MLC-05E")
      (footprint "varistor")
      (description "TVS Varistor, 8 V, 5 V, ChipGuard MLC, 20 V, 0603 [1608 Metric], Multilayer Varistor (MLV)")
      (fields (field (name "MANUFACTURER") "Bourns") (field (name "VOLTAGE") "5V"))
      (libsource (lib "Schlib") (part "CG0603MLC-05E"))
    )
    (comp (ref "Z2")
      (value "CG0603MLC-05E")
      (footprint "varistor")
      (description "TVS Varistor, 8 V, 5 V, ChipGuard MLC, 20 V, 0603 [1608 Metric], Multilayer Varistor (MLV)")
      (fields (field (name "MANUFACTURER") "Bourns") (field (name "VOLTAGE") "5V"))
      (libsource (lib "Schlib") (part "CG0603MLC-05E"))
    )
  )
  (nets
    (net (code "1") (name "+3V3") (class "Default")
      (node (ref "C17") (pin "2") (pinfunction "2_2") (pintype "passive"))
      (node (ref "C2") (pin "2") (pinfunction "2_2") (pintype "passive"))
      (node (ref "J1") (pin "4") (pinfunction "4_4") (pintype "passive"))
      (node (ref "J7") (pin "1") (pinfunction "1_1") (pintype "passive"))
      (node (ref "U1") (pin "4") (pinfunction "OUT_4") (pintype "passive"))
      (node (ref "U1") (pin "5") (pinfunction "SENSE_5") (pintype "passive"))
    )
    (net (code "2") (name "+5V") (class "Default")
      (node (ref "C1") (pin "2") (pinfunction "2_2") (pintype "passive"))
      (node (ref "C12") (pin "1") (pinfunction "+_1") (pintype "passive"))
      (node (ref "C15") (pin "2") (pinfunction "2_2") (pintype "passive"))
      (node (ref "C21") (pin "2") (pinfunction "2_2") (pintype "passive"))
      (node (ref "J1") (pin "5") (pinfunction "5_5") (pintype "passive"))
      (node (ref "J7") (pin "3") (pinfunction "3_3") (pintype "passive"))
      (node (ref "L1") (pin "14") (pinfunction "14_14") (pintype "passive"))
      (node (ref "P1") (pin "1") (pinfunction "1_1") (pintype "passive"))
      (node (ref "R3") (pin "2") (pinfunction "2_2") (pintype "passive"))
      (node (ref "U1") (pin "1") (pinfunction "SHDN_1") (pintype "passive"))
      (node (ref "U1") (pin "2") (pinfunction "IN_2") (pintype "passive"))
      (node (ref "U3") (pin "31") (pinfunction "UVCC_31") (pintype "passive"))
    )
    (net (code "3") (name "+5{slash}3V3") (class "Default")
      (node (ref "C14") (pin "1") (pinfunction "1_1") (pintype "passive"))
      (node (ref "C16") (pin "2") (pinfunction "2_2") (pintype "passive"))
      (node (ref "C23") (pin "2") (pinfunction "2_2") (pintype "passive"))
      (node (ref "C24") (pin "2") (pinfunction "2_2") (pintype "passive"))
      (node (ref "C25") (pin "2") (pinfunction "2_2") (pintype "passive"))
      (node (ref "C30") (pin "2") (pinfunction "2_2") (pintype "passive"))
      (node (ref "C31") (pin "2") (pinfunction "2_2") (pintype "passive"))
      (node (ref "C34") (pin "2") (pinfunction "2_2") (pintype "passive"))
      (node (ref "D1") (pin "2") (pinfunction "anode_2") (pintype "passive"))
      (node (ref "D2") (pin "2") (pinfunction "anode_2") (pintype "passive"))
      (node (ref "D5") (pin "1") (pinfunction "cathode_1") (pintype "passive"))
      (node (ref "D6") (pin "1") (pinfunction "cathode_1") (pintype "passive"))
      (node (ref "FB1") (pin "1") (pinfunction "1_1") (pintype "passive"))
      (node (ref "FB2") (pin "1") (pinfunction "1_1") (pintype "passive"))
      (node (ref "FB3") (pin "1") (pinfunction "1_1") (pintype "passive"))
      (node (ref "J1") (pin "2") (pinfunction "2_2") (pintype "passive"))
      (node (ref "J5") (pin "2") (pinfunction "2_2") (pintype "passive"))
      (node (ref "J6") (pin "2") (pinfunction "2_2") (pintype "passive"))
      (node (ref "J7") (pin "2") (pinfunction "2_2") (pintype "passive"))
      (node (ref "R11") (pin "2") (pinfunction "2_2") (pintype "passive"))
      (node (ref "R14") (pin "2") (pinfunction "2_2") (pintype "passive"))
      (node (ref "R17") (pin "2") (pinfunction "2_2") (pintype "passive"))
      (node (ref "R18") (pin "2") (pinfunction "2_2") (pintype "passive"))
      (node (ref "R19") (pin "2") (pinfunction "2_2") (pintype "passive"))
      (node (ref "R20") (pin "2") (pinfunction "2_2") (pintype "passive"))
      (node (ref "R8") (pin "2") (pinfunction "2_2") (pintype "passive"))
      (node (ref "R9") (pin "2") (pinfunction "2_2") (pintype "passive"))
      (node (ref "U4") (pin "5") (pinfunction "5_5") (pintype "passive"))
      (node (ref "U5") (pin "5") (pinfunction "5_5") (pintype "passive"))
      (node (ref "U6") (pin "5") (pinfunction "5_5") (pintype "passive"))
      (node (ref "U7") (pin "5") (pinfunction "5_5") (pintype "passive"))
    )
    (net (code "4") (name "+AREF") (class "Default")
      (node (ref "C20") (pin "1") (pinfunction "1_1") (pintype "passive"))
      (node (ref "C22") (pin "2") (pinfunction "2_2") (pintype "passive"))
      (node (ref "J2") (pin "8") (pinfunction "8_8") (pintype "passive"))
      (node (ref "U2") (pin "21") (pinfunction "AREF_21") (pintype "passive"))
    )
    (net (code "5") (name "/+3V3_16U2_UCAP") (class "Default")
      (node (ref "C32") (pin "1") (pinfunction "1_1") (pintype "passive"))
      (node (ref "U3") (pin "27") (pinfunction "UCAP_27") (pintype "passive"))
    )
    (net (code "6") (name "/+5_USB") (class "Default")
      (node (ref "C13") (pin "1") (pinfunction "+_1") (pintype "passive"))
      (node (ref "L1") (pin "15") (pinfunction "15_15") (pintype "passive"))
      (node (ref "USB") (pin "1") (pinfunction "1_1") (pintype "passive"))
    )
    (net (code "7") (name "/16U2PROG_328P_RESETn") (class "Default")
      (node (ref "J10") (pin "2") (pinfunction "2_2") (pintype "passive"))
      (node (ref "R3") (pin "1") (pinfunction "1_1") (pintype "passive"))
      (node (ref "U3") (pin "13") (pinfunction "(HWB_/_AIN6_/_T0_/_INT7)_PD7_13") (pintype "passive"))
    )
    (net (code "8") (name "/16U2_HDR_RESETn") (class "Default")
      (node (ref "J5") (pin "5") (pinfunction "5_5") (pintype "passive"))
      (node (ref "J8") (pin "3") (pinfunction "3_3") (pintype "passive"))
    )
    (net (code "9") (name "/16U2_MISO") (class "Default")
      (node (ref "J5") (pin "1") (pinfunction "1_1") (pintype "passive"))
      (node (ref "U3") (pin "17") (pinfunction "(PDO_/_MISO_/_PCINT3)_PB3_17") (pintype "passive"))
    )
    (net (code "10") (name "/16U2_MOSI") (class "Default")
      (node (ref "J5") (pin "4") (pinfunction "4_4") (pintype "passive"))
      (node (ref "U3") (pin "16") (pinfunction "(PDI_/_MOSI_/_PCINT2)_PB2_16") (pintype "passive"))
    )
    (net (code "11") (name "/16U2_PB4") (class "Default")
      (node (ref "J8") (pin "2") (pinfunction "2_2") (pintype "passive"))
      (node (ref "U3") (pin "18") (pinfunction "(T1_/_PCINT4)_PB4_18") (pintype "passive"))
    )
    (net (code "12") (name "/16U2_RESETn") (class "Default")
      (node (ref "J8") (pin "4") (pinfunction "4_4") (pintype "passive"))
      (node (ref "R8") (pin "1") (pinfunction "1_1") (pintype "passive"))
      (node (ref "U3") (pin "24") (pinfunction "Reset_(PC1_/_dW)_24") (pintype "passive"))
      (node (ref "U5") (pin "4") (pinfunction "4_4") (pintype "output"))
    )
    (net (code "13") (name "/16U2_RXD") (class "Default")
      (node (ref "R12") (pin "1") (pinfunction "1_1") (pintype "passive"))
      (node (ref "U3") (pin "8") (pinfunction "(RXD1_/_AIN1_/_INT2)_PD2_8") (pintype "passive"))
    )
    (net (code "14") (name "/16U2_RX_LED") (class "Default")
      (node (ref "D2") (pin "1") (pinfunction "cathode_1") (pintype "passive"))
      (node (ref "U3") (pin "10") (pinfunction "(INT5/_AIN3)_PD4_10") (pintype "passive"))
    )
    (net (code "15") (name "/16U2_SCLK") (class "Default")
      (node (ref "J5") (pin "3") (pinfunction "3_3") (pintype "passive"))
      (node (ref "R10") (pin "2") (pinfunction "2_2") (pintype "passive"))
    )
    (net (code "16") (name "/16U2_SCLK_R") (class "Default")
      (node (ref "R10") (pin "1") (pinfunction "1_1") (pintype "passive"))
      (node (ref "U3") (pin "15") (pinfunction "(SCLK_/_PCINT1)_PB1_15") (pintype "passive"))
    )
    (net (code "17") (name "/16U2_TXD") (class "Default")
      (node (ref "R13") (pin "2") (pinfunction "2_2") (pintype "passive"))
      (node (ref "U3") (pin "9") (pinfunction "(TXD1_/_INT3)_PD3_9") (pintype "passive"))
    )
    (net (code "18") (name "/16U2_TX_LED") (class "Default")
      (node (ref "D1") (pin "1") (pinfunction "cathode_1") (pintype "passive"))
      (node (ref "U3") (pin "11") (pinfunction "(XCK_AIN4_/_PCINT12)_PD5_11") (pintype "passive"))
    )
    (net (code "19") (name "/328P_AUTORESETn") (class "Default")
      (node (ref "C27") (pin "2") (pinfunction "2_2") (pintype "passive"))
      (node (ref "R19") (pin "1") (pinfunction "1_1") (pintype "passive"))
      (node (ref "U6") (pin "1") (pinfunction "1_1") (pintype "input"))
    )
    (net (code "20") (name "/328P_RESETn") (class "Default")
      (node (ref "J1") (pin "3") (pinfunction "3_3") (pintype "passive"))
      (node (ref "J6") (pin "5") (pinfunction "5_5") (pintype "passive"))
      (node (ref "J8") (pin "1") (pinfunction "1_1") (pintype "passive"))
      (node (ref "R9") (pin "1") (pinfunction "1_1") (pintype "passive"))
      (node (ref "U2") (pin "1") (pinfunction "PC6_(PCINT14/RESET)_1") (pintype "passive"))
      (node (ref "U6") (pin "4") (pinfunction "4_4") (pintype "output"))
    )
    (net (code "21") (name "/AVCC") (class "Default")
      (node (ref "C8") (pin "1") (pinfunction "1_1") (pintype "passive"))
      (node (ref "C9") (pin "2") (pinfunction "2_2") (pintype "passive"))
      (node (ref "FB3") (pin "2") (pinfunction "2_2") (pintype "passive"))
      (node (ref "U2") (pin "20") (pinfunction "AVCC_20") (pintype "passive"))
    )
    (net (code "22") (name "/BUTTON_RESETn") (class "Default")
      (node (ref "D6") (pin "2") (pinfunction "anode_2") (pintype "passive"))
      (node (ref "R20") (pin "1") (pinfunction "1_1") (pintype "passive"))
      (node (ref "R24") (pin "1") (pinfunction "1_1") (pintype "passive"))
      (node (ref "SW2") (pin "3") (pinfunction "3_3") (pintype "passive"))
      (node (ref "SW2") (pin "4") (pinfunction "4_4") (pintype "passive"))
    )
    (net (code "23") (name "/CON_USB_N") (class "Default")
      (node (ref "R1") (pin "1") (pinfunction "1_1") (pintype "passive"))
      (node (ref "USB") (pin "2") (pinfunction "2_2") (pintype "passive"))
      (node (ref "Z1") (pin "13") (pinfunction "13_13") (pintype "passive"))
    )
    (net (code "24") (name "/CON_USB_P") (class "Default")
      (node (ref "R2") (pin "1") (pinfunction "1_1") (pintype "passive"))
      (node (ref "USB") (pin "3") (pinfunction "3_3") (pintype "passive"))
      (node (ref "Z2") (pin "13") (pinfunction "13_13") (pintype "passive"))
    )
    (net (code "25") (name "/PB0") (class "Default")
      (node (ref "J2") (pin "1") (pinfunction "1_1") (pintype "passive"))
      (node (ref "R22") (pin "2") (pinfunction "2_2") (pintype "passive"))
      (node (ref "U2") (pin "14") (pinfunction "PB0_(PCINT0/CLKO/ICP1)_14") (pintype "passive"))
    )
    (net (code "26") (name "/PB1") (class "Default")
      (node (ref "J2") (pin "2") (pinfunction "2_2") (pintype "passive"))
      (node (ref "U2") (pin "15") (pinfunction "PB1_(OC1A/PCINT1)_15") (pintype "passive"))
    )
    (net (code "27") (name "/PB2") (class "Default")
      (node (ref "J2") (pin "3") (pinfunction "3_3") (pintype "passive"))
      (node (ref "U2") (pin "16") (pinfunction "PB2_(SS/OC1B/PCINT2)_16") (pintype "passive"))
    )
    (net (code "28") (name "/PB3") (class "Default")
      (node (ref "J2") (pin "4") (pinfunction "4_4") (pintype "passive"))
      (node (ref "J6") (pin "4") (pinfunction "4_4") (pintype "passive"))
      (node (ref "U2") (pin "17") (pinfunction "PB3_(MOSI/OC2A/PCINT3)_17") (pintype "passive"))
    )
    (net (code "29") (name "/PB4") (class "Default")
      (node (ref "J2") (pin "5") (pinfunction "5_5") (pintype "passive"))
      (node (ref "J6") (pin "1") (pinfunction "1_1") (pintype "passive"))
      (node (ref "U2") (pin "18") (pinfunction "PB4_(MISO/PCINT4)_18") (pintype "passive"))
    )
    (net (code "30") (name "/PB5") (class "Default")
      (node (ref "J2") (pin "6") (pinfunction "6_6") (pintype "passive"))
      (node (ref "J6") (pin "3") (pinfunction "3_3") (pintype "passive"))
      (node (ref "R7") (pin "2") (pinfunction "2_2") (pintype "passive"))
      (node (ref "U4") (pin "1") (pinfunction "1_1") (pintype "input"))
      (node (ref "U4") (pin "2") (pinfunction "2_2") (pintype "input"))
    )
    (net (code "31") (name "/PB5R") (class "Default")
      (node (ref "R7") (pin "1") (pinfunction "1_1") (pintype "passive"))
      (node (ref "U2") (pin "19") (pinfunction "PB5_(SCK/PCINT5)_19") (pintype "passive"))
    )
    (net (code "32") (name "/PC0") (class "Default")
      (node (ref "J3") (pin "1") (pinfunction "1_1") (pintype "passive"))
      (node (ref "U2") (pin "23") (pinfunction "PC0_(ADC0/PCINT8)_23") (pintype "passive"))
    )
    (net (code "33") (name "/PC1") (class "Default")
      (node (ref "J3") (pin "2") (pinfunction "2_2") (pintype "passive"))
      (node (ref "U2") (pin "24") (pinfunction "PC1_(ADC1/PCINT9)_24") (pintype "passive"))
    )
    (net (code "34") (name "/PC2") (class "Default")
      (node (ref "J3") (pin "3") (pinfunction "3_3") (pintype "passive"))
      (node (ref "U2") (pin "25") (pinfunction "PC2_(ADC2/PCINT10)_25") (pintype "passive"))
    )
    (net (code "35") (name "/PC3") (class "Default")
      (node (ref "J3") (pin "4") (pinfunction "4_4") (pintype "passive"))
      (node (ref "U2") (pin "26") (pinfunction "PC3_(ADC3/PCINT11)_26") (pintype "passive"))
    )
    (net (code "36") (name "/PC4") (class "Default")
      (node (ref "J2") (pin "9") (pinfunction "9_9") (pintype "passive"))
      (node (ref "J3") (pin "5") (pinfunction "5_5") (pintype "passive"))
      (node (ref "U2") (pin "27") (pinfunction "PC4_(ADC4/SDA/PCINT12)_27") (pintype "passive"))
    )
    (net (code "37") (name "/PC5") (class "Default")
      (node (ref "J2") (pin "10") (pinfunction "10_10") (pintype "passive"))
      (node (ref "J3") (pin "6") (pinfunction "6_6") (pintype "passive"))
      (node (ref "U2") (pin "28") (pinfunction "PC5_(ADC5/SCL/PCINT13)_28") (pintype "passive"))
    )
    (net (code "38") (name "/PD0") (class "Default")
      (node (ref "J4") (pin "1") (pinfunction "1_1") (pintype "passive"))
      (node (ref "R12") (pin "2") (pinfunction "2_2") (pintype "passive"))
      (node (ref "U2") (pin "2") (pinfunction "(PCINT16/RXD)_PD0_2") (pintype "passive"))
    )
    (net (code "39") (name "/PD1") (class "Default")
      (node (ref "J4") (pin "2") (pinfunction "2_2") (pintype "passive"))
      (node (ref "R13") (pin "1") (pinfunction "1_1") (pintype "passive"))
      (node (ref "U2") (pin "3") (pinfunction "(PCINT17/TXD)_PD1_3") (pintype "passive"))
    )
    (net (code "40") (name "/PD2") (class "Default")
      (node (ref "J4") (pin "3") (pinfunction "3_3") (pintype "passive"))
      (node (ref "U2") (pin "4") (pinfunction "(PCINT18/INT0)_PD2_4") (pintype "passive"))
    )
    (net (code "41") (name "/PD3") (class "Default")
      (node (ref "J4") (pin "4") (pinfunction "4_4") (pintype "passive"))
      (node (ref "U2") (pin "5") (pinfunction "(PCINT19/OC2B/INT1)_PD3_5") (pintype "passive"))
    )
    (net (code "42") (name "/PD4") (class "Default")
      (node (ref "J4") (pin "5") (pinfunction "5_5") (pintype "passive"))
      (node (ref "U2") (pin "6") (pinfunction "(PCINT20/XCK/T0)_PD4_6") (pintype "passive"))
    )
    (net (code "43") (name "/PD5") (class "Default")
      (node (ref "J4") (pin "6") (pinfunction "6_6") (pintype "passive"))
      (node (ref "U2") (pin "11") (pinfunction "(PCINT21/OC0B/T1)_PD5_11") (pintype "passive"))
    )
    (net (code "44") (name "/PD6") (class "Default")
      (node (ref "J4") (pin "7") (pinfunction "7_7") (pintype "passive"))
      (node (ref "U2") (pin "12") (pinfunction "(PCINT22/OC0A/AIN0)_PD6_12") (pintype "passive"))
    )
    (net (code "45") (name "/PD7") (class "Default")
      (node (ref "J4") (pin "8") (pinfunction "8_8") (pintype "passive"))
      (node (ref "U2") (pin "13") (pinfunction "(PCINT23/AIN1)_PD7_13") (pintype "passive"))
    )
    (net (code "46") (name "/USB_N") (class "Default")
      (node (ref "R1") (pin "2") (pinfunction "2_2") (pintype "passive"))
      (node (ref "U3") (pin "30") (pinfunction "D-_30") (pintype "passive"))
    )
    (net (code "47") (name "/USB_P") (class "Default")
      (node (ref "R2") (pin "2") (pinfunction "2_2") (pintype "passive"))
      (node (ref "U3") (pin "29") (pinfunction "D+_29") (pintype "passive"))
    )
    (net (code "48") (name "/USER_BUTTON") (class "Default")
      (node (ref "R18") (pin "1") (pinfunction "1_1") (pintype "passive"))
      (node (ref "R23") (pin "1") (pinfunction "1_1") (pintype "passive"))
      (node (ref "SW1") (pin "3") (pinfunction "3_3") (pintype "passive"))
      (node (ref "SW1") (pin "4") (pinfunction "4_4") (pintype "passive"))
    )
    (net (code "49") (name "/USER_BUTTON_BUF") (class "Default")
      (node (ref "C29") (pin "1") (pinfunction "1_1") (pintype "passive"))
      (node (ref "R23") (pin "2") (pinfunction "2_2") (pintype "passive"))
      (node (ref "U7") (pin "1") (pinfunction "1_1") (pintype "input"))
      (node (ref "U7") (pin "2") (pinfunction "2_2") (pintype "input"))
    )
    (net (code "50") (name "/VCC") (class "Default")
      (node (ref "C3") (pin "1") (pinfunction "1_1") (pintype "passive"))
      (node (ref "C4") (pin "2") (pinfunction "2_2") (pintype "passive"))
      (node (ref "FB1") (pin "2") (pinfunction "2_2") (pintype "passive"))
      (node (ref "U2") (pin "7") (pinfunction "VCC_7") (pintype "passive"))
    )
    (net (code "51") (name "/VCC_16U2") (class "Default")
      (node (ref "C5") (pin "1") (pinfunction "1_1") (pintype "passive"))
      (node (ref "C6") (pin "2") (pinfunction "2_2") (pintype "passive"))
      (node (ref "C7") (pin "2") (pinfunction "2_2") (pintype "passive"))
      (node (ref "FB2") (pin "2") (pinfunction "2_2") (pintype "passive"))
      (node (ref "U3") (pin "32") (pinfunction "AVCC_32") (pintype "passive"))
      (node (ref "U3") (pin "4") (pinfunction "VCC_4") (pintype "passive"))
    )
    (net (code "52") (name "/XTAL1") (class "Default")
      (node (ref "C18") (pin "1") (pinfunction "1_1") (pintype "passive"))
      (node (ref "R5") (pin "1") (pinfunction "1_1") (pintype "passive"))
      (node (ref "U2") (pin "9") (pinfunction "PB6_(PCINT6/XTAL1/TOSC1)_9") (pintype "passive"))
      (node (ref "Y1") (pin "1") (pinfunction "1_1") (pintype "passive"))
    )
    (net (code "53") (name "/XTAL1_16U2") (class "Default")
      (node (ref "C19") (pin "1") (pinfunction "1_1") (pintype "passive"))
      (node (ref "R6") (pin "1") (pinfunction "1_1") (pintype "passive"))
      (node (ref "U3") (pin "1") (pinfunction "XTAL1_1") (pintype "passive"))
      (node (ref "Y2") (pin "1") (pinfunction "1_1") (pintype "passive"))
    )
    (net (code "54") (name "/XTAL2") (class "Default")
      (node (ref "C10") (pin "1") (pinfunction "1_1") (pintype "passive"))
      (node (ref "R5") (pin "2") (pinfunction "2_2") (pintype "passive"))
      (node (ref "U2") (pin "10") (pinfunction "PB7_(PCINT7/XTAL2/TOSC2)_10") (pintype "passive"))
      (node (ref "Y1") (pin "2") (pinfunction "2_2") (pintype "passive"))
    )
    (net (code "55") (name "/XTAL2_16U2") (class "Default")
      (node (ref "C11") (pin "1") (pinfunction "1_1") (pintype "passive"))
      (node (ref "R6") (pin "2") (pinfunction "2_2") (pintype "passive"))
      (node (ref "U3") (pin "2") (pinfunction "XTAL2_(PC0)_2") (pintype "passive"))
      (node (ref "Y2") (pin "2") (pinfunction "2_2") (pintype "passive"))
    )
    (net (code "56") (name "GND") (class "Default")
      (node (ref "C1") (pin "1") (pinfunction "1_1") (pintype "passive"))
      (node (ref "C10") (pin "2") (pinfunction "2_2") (pintype "passive"))
      (node (ref "C11") (pin "2") (pinfunction "2_2") (pintype "passive"))
      (node (ref "C12") (pin "2") (pinfunction "1_2") (pintype "passive"))
      (node (ref "C13") (pin "2") (pinfunction "1_2") (pintype "passive"))
      (node (ref "C14") (pin "2") (pinfunction "2_2") (pintype "passive"))
      (node (ref "C15") (pin "1") (pinfunction "1_1") (pintype "passive"))
      (node (ref "C16") (pin "1") (pinfunction "1_1") (pintype "passive"))
      (node (ref "C17") (pin "1") (pinfunction "1_1") (pintype "passive"))
      (node (ref "C18") (pin "2") (pinfunction "2_2") (pintype "passive"))
      (node (ref "C19") (pin "2") (pinfunction "2_2") (pintype "passive"))
      (node (ref "C2") (pin "1") (pinfunction "1_1") (pintype "passive"))
      (node (ref "C20") (pin "2") (pinfunction "2_2") (pintype "passive"))
      (node (ref "C21") (pin "1") (pinfunction "1_1") (pintype "passive"))
      (node (ref "C22") (pin "1") (pinfunction "1_1") (pintype "passive"))
      (node (ref "C23") (pin "1") (pinfunction "1_1") (pintype "passive"))
      (node (ref "C24") (pin "1") (pinfunction "1_1") (pintype "passive"))
      (node (ref "C25") (pin "1") (pinfunction "1_1") (pintype "passive"))
      (node (ref "C28") (pin "2") (pinfunction "2_2") (pintype "passive"))
      (node (ref "C29") (pin "2") (pinfunction "2_2") (pintype "passive"))
      (node (ref "C3") (pin "2") (pinfunction "2_2") (pintype "passive"))
      (node (ref "C30") (pin "1") (pinfunction "1_1") (pintype "passive"))
      (node (ref "C31") (pin "1") (pinfunction "1_1") (pintype "passive"))
      (node (ref "C32") (pin "2") (pinfunction "2_2") (pintype "passive"))
      (node (ref "C33") (pin "2") (pinfunction "2_2") (pintype "passive"))
      (node (ref "C34") (pin "1") (pinfunction "1_1") (pintype "passive"))
      (node (ref "C4") (pin "1") (pinfunction "1_1") (pintype "passive"))
      (node (ref "C5") (pin "2") (pinfunction "2_2") (pintype "passive"))
      (node (ref "C6") (pin "1") (pinfunction "1_1") (pintype "passive"))
      (node (ref "C7") (pin "1") (pinfunction "1_1") (pintype "passive"))
      (node (ref "C8") (pin "2") (pinfunction "2_2") (pintype "passive"))
      (node (ref "C9") (pin "1") (pinfunction "1_1") (pintype "passive"))
      (node (ref "D4") (pin "1") (pinfunction "cathode_1") (pintype "passive"))
      (node (ref "J1") (pin "6") (pinfunction "6_6") (pintype "passive"))
      (node (ref "J1") (pin "7") (pinfunction "7_7") (pintype "passive"))
      (node (ref "J2") (pin "7") (pinfunction "7_7") (pintype "passive"))
      (node (ref "J5") (pin "6") (pinfunction "6_6") (pintype "passive"))
      (node (ref "J6") (pin "6") (pinfunction "6_6") (pintype "passive"))
      (node (ref "MH1") (pin "1") (pinfunction "1_1") (pintype "passive"))
      (node (ref "MH2") (pin "1") (pinfunction "1_1") (pintype "passive"))
      (node (ref "MH3") (pin "1") (pinfunction "1_1") (pintype "passive"))
      (node (ref "P2") (pin "1") (pinfunction "1_1") (pintype "passive"))
      (node (ref "R16") (pin "1") (pinfunction "1_1") (pintype "passive"))
      (node (ref "R4") (pin "1") (pinfunction "1_1") (pintype "passive"))
      (node (ref "SW1") (pin "1") (pinfunction "1_1") (pintype "passive"))
      (node (ref "SW1") (pin "2") (pinfunction "2_2") (pintype "passive"))
      (node (ref "SW2") (pin "1") (pinfunction "1_1") (pintype "passive"))
      (node (ref "SW2") (pin "2") (pinfunction "2_2") (pintype "passive"))
      (node (ref "U1") (pin "3") (pinfunction "GND_3") (pintype "passive"))
      (node (ref "U1") (pin "6") (pinfunction "EPAD_6") (pintype "passive"))
      (node (ref "U2") (pin "22") (pinfunction "GND_22") (pintype "passive"))
      (node (ref "U2") (pin "8") (pinfunction "GND_8") (pintype "passive"))
      (node (ref "U3") (pin "28") (pinfunction "UGND_28") (pintype "passive"))
      (node (ref "U3") (pin "3") (pinfunction "GND_3") (pintype "passive"))
      (node (ref "U4") (pin "3") (pinfunction "3_3") (pintype "passive"))
      (node (ref "U5") (pin "3") (pinfunction "3_3") (pintype "passive"))
      (node (ref "U6") (pin "3") (pinfunction "3_3") (pintype "passive"))
      (node (ref "U7") (pin "3") (pinfunction "3_3") (pintype "passive"))
      (node (ref "USB") (pin "5") (pinfunction "5_5") (pintype "passive"))
      (node (ref "USB") (pin "S1") (pinfunction "6_S1") (pintype "passive"))
      (node (ref "USB") (pin "S2") (pinfunction "7_S2") (pintype "passive"))
      (node (ref "USB") (pin "S3") (pinfunction "8_S3") (pintype "passive"))
      (node (ref "USB") (pin "S4") (pinfunction "9_S4") (pintype "passive"))
      (node (ref "USB") (pin "S5") (pinfunction "10_S5") (pintype "passive"))
      (node (ref "USB") (pin "S6") (pinfunction "11_S6") (pintype "passive"))
      (node (ref "Z1") (pin "12") (pinfunction "12_12") (pintype "passive"))
      (node (ref "Z2") (pin "12") (pinfunction "12_12") (pintype "passive"))
    )
    (net (code "57") (name "Net-(C27-Pad1)") (class "Default")
      (node (ref "C27") (pin "1") (pinfunction "1_1") (pintype "passive"))
      (node (ref "J10") (pin "1") (pinfunction "1_1") (pintype "passive"))
    )
    (net (code "58") (name "Net-(C28-Pad1)") (class "Default")
      (node (ref "C28") (pin "1") (pinfunction "1_1") (pintype "passive"))
      (node (ref "R21") (pin "2") (pinfunction "2_2") (pintype "passive"))
      (node (ref "U5") (pin "1") (pinfunction "1_1") (pintype "input"))
      (node (ref "U5") (pin "2") (pinfunction "2_2") (pintype "input"))
    )
    (net (code "59") (name "Net-(C33-Pad1)") (class "Default")
      (node (ref "C33") (pin "1") (pinfunction "1_1") (pintype "passive"))
      (node (ref "R24") (pin "2") (pinfunction "2_2") (pintype "passive"))
      (node (ref "U6") (pin "2") (pinfunction "2_2") (pintype "input"))
    )
    (net (code "60") (name "Net-(D3-anode)") (class "Default")
      (node (ref "D3") (pin "2") (pinfunction "anode_2") (pintype "passive"))
      (node (ref "R11") (pin "1") (pinfunction "1_1") (pintype "passive"))
    )
    (net (code "61") (name "Net-(D3-cathode)") (class "Default")
      (node (ref "D3") (pin "1") (pinfunction "cathode_1") (pintype "passive"))
      (node (ref "U4") (pin "4") (pinfunction "4_4") (pintype "output"))
    )
    (net (code "62") (name "Net-(D4-anode)") (class "Default")
      (node (ref "D4") (pin "2") (pinfunction "anode_2") (pintype "passive"))
      (node (ref "R14") (pin "1") (pinfunction "1_1") (pintype "passive"))
    )
    (net (code "63") (name "Net-(D5-anode)") (class "Default")
      (node (ref "D5") (pin "2") (pinfunction "anode_2") (pintype "passive"))
      (node (ref "R17") (pin "1") (pinfunction "1_1") (pintype "passive"))
      (node (ref "R21") (pin "1") (pinfunction "1_1") (pintype "passive"))
    )
    (net (code "64") (name "Net-(J10-Pad3)") (class "Default")
      (node (ref "J10") (pin "3") (pinfunction "3_3") (pintype "passive"))
      (node (ref "R16") (pin "2") (pinfunction "2_2") (pintype "passive"))
    )
    (net (code "65") (name "Net-(R4-Pad2)") (class "Default")
      (node (ref "R4") (pin "2") (pinfunction "2_2") (pintype "passive"))
      (node (ref "USB") (pin "4") (pinfunction "4_4") (pintype "passive"))
    )
    (net (code "66") (name "Net-(R22-Pad1)") (class "Default")
      (node (ref "R22") (pin "1") (pinfunction "1_1") (pintype "passive"))
      (node (ref "U7") (pin "4") (pinfunction "4_4") (pintype "output"))
    )
    (net (code "67") (name "unconnected-(J1-Pad1)") (class "Default")
      (node (ref "J1") (pin "1") (pinfunction "1_1") (pintype "passive+no_connect"))
    )
    (net (code "68") (name "unconnected-(J1-Pad8)") (class "Default")
      (node (ref "J1") (pin "8") (pinfunction "8_8") (pintype "passive+no_connect"))
    )
    (net (code "69") (name "unconnected-(MH4-Pad1)") (class "Default")
      (node (ref "MH4") (pin "1") (pinfunction "1_1") (pintype "passive+no_connect"))
    )
    (net (code "70") (name "unconnected-(U3-(AIN0_{slash}_INT1)_PD1-Pad7)") (class "Default")
      (node (ref "U3") (pin "7") (pinfunction "(AIN0_/_INT1)_PD1_7") (pintype "passive+no_connect"))
    )
    (net (code "71") (name "unconnected-(U3-(INT4_{slash}_ICP1_{slash}_CLKO)_PC7-Pad22)") (class "Default")
      (node (ref "U3") (pin "22") (pinfunction "(INT4_/_ICP1_/_CLKO)_PC7_22") (pintype "passive+no_connect"))
    )
    (net (code "72") (name "unconnected-(U3-(OC.0B_{slash}_INT0)_PD0-Pad6)") (class "Default")
      (node (ref "U3") (pin "6") (pinfunction "(OC.0B_/_INT0)_PD0_6") (pintype "passive+no_connect"))
    )
    (net (code "73") (name "unconnected-(U3-(OC.1A_{slash}_PCINT8)_PC6-Pad23)") (class "Default")
      (node (ref "U3") (pin "23") (pinfunction "(OC.1A_/_PCINT8)_PC6_23") (pintype "passive+no_connect"))
    )
    (net (code "74") (name "unconnected-(U3-(PCINT5)_PB5-Pad19)") (class "Default")
      (node (ref "U3") (pin "19") (pinfunction "(PCINT5)_PB5_19") (pintype "passive+no_connect"))
    )
    (net (code "75") (name "unconnected-(U3-(PCINT7_{slash}_OC.0A_{slash}_OC.1C)_PB7-Pad21)") (class "Default")
      (node (ref "U3") (pin "21") (pinfunction "(PCINT7_/_OC.0A_/_OC.1C)_PB7_21") (pintype "passive+no_connect"))
    )
    (net (code "76") (name "unconnected-(U3-(PCINT10)_PC4-Pad26)") (class "Default")
      (node (ref "U3") (pin "26") (pinfunction "(PCINT10)_PC4_26") (pintype "passive+no_connect"))
    )
    (net (code "77") (name "unconnected-(U3-(PCINT11_{slash}AIN2_)_PC2-Pad5)") (class "Default")
      (node (ref "U3") (pin "5") (pinfunction "(PCINT11_/AIN2_)_PC2_5") (pintype "passive+no_connect"))
    )
    (net (code "78") (name "unconnected-(U3-(RTS_{slash}_AIN5_{slash}_INT6)_PD6-Pad12)") (class "Default")
      (node (ref "U3") (pin "12") (pinfunction "(RTS_/_AIN5_/_INT6)_PD6_12") (pintype "passive+no_connect"))
    )
    (net (code "79") (name "unconnected-(U3-(SS_{slash}_PCINT0)_PB0-Pad14)") (class "Default")
      (node (ref "U3") (pin "14") (pinfunction "(SS_/_PCINT0)_PB0_14") (pintype "passive+no_connect"))
    )
    (net (code "80") (name "unconnected-(U3-(_PCINT9{slash}_OC.1B)_PC5-Pad25)") (class "Default")
      (node (ref "U3") (pin "25") (pinfunction "(_PCINT9/_OC.1B)_PC5_25") (pintype "passive+no_connect"))
    )
    (net (code "81") (name "unconnected-(U3-Thermal_PAD-Pad33)") (class "Default")
      (node (ref "U3") (pin "33") (pinfunction "Thermal_PAD_33") (pintype "passive"))
    )
    (net (code "82") (name "unconnected-(U3-_(PCINT6)_PB6-Pad20)") (class "Default")
      (node (ref "U3") (pin "20") (pinfunction "_(PCINT6)_PB6_20") (pintype "passive+no_connect"))
    )
  )
)
